# SCH_Rydful-Beacon_2026-01-27.net
KiCad netlist of a schematic drawn in EasyEDA
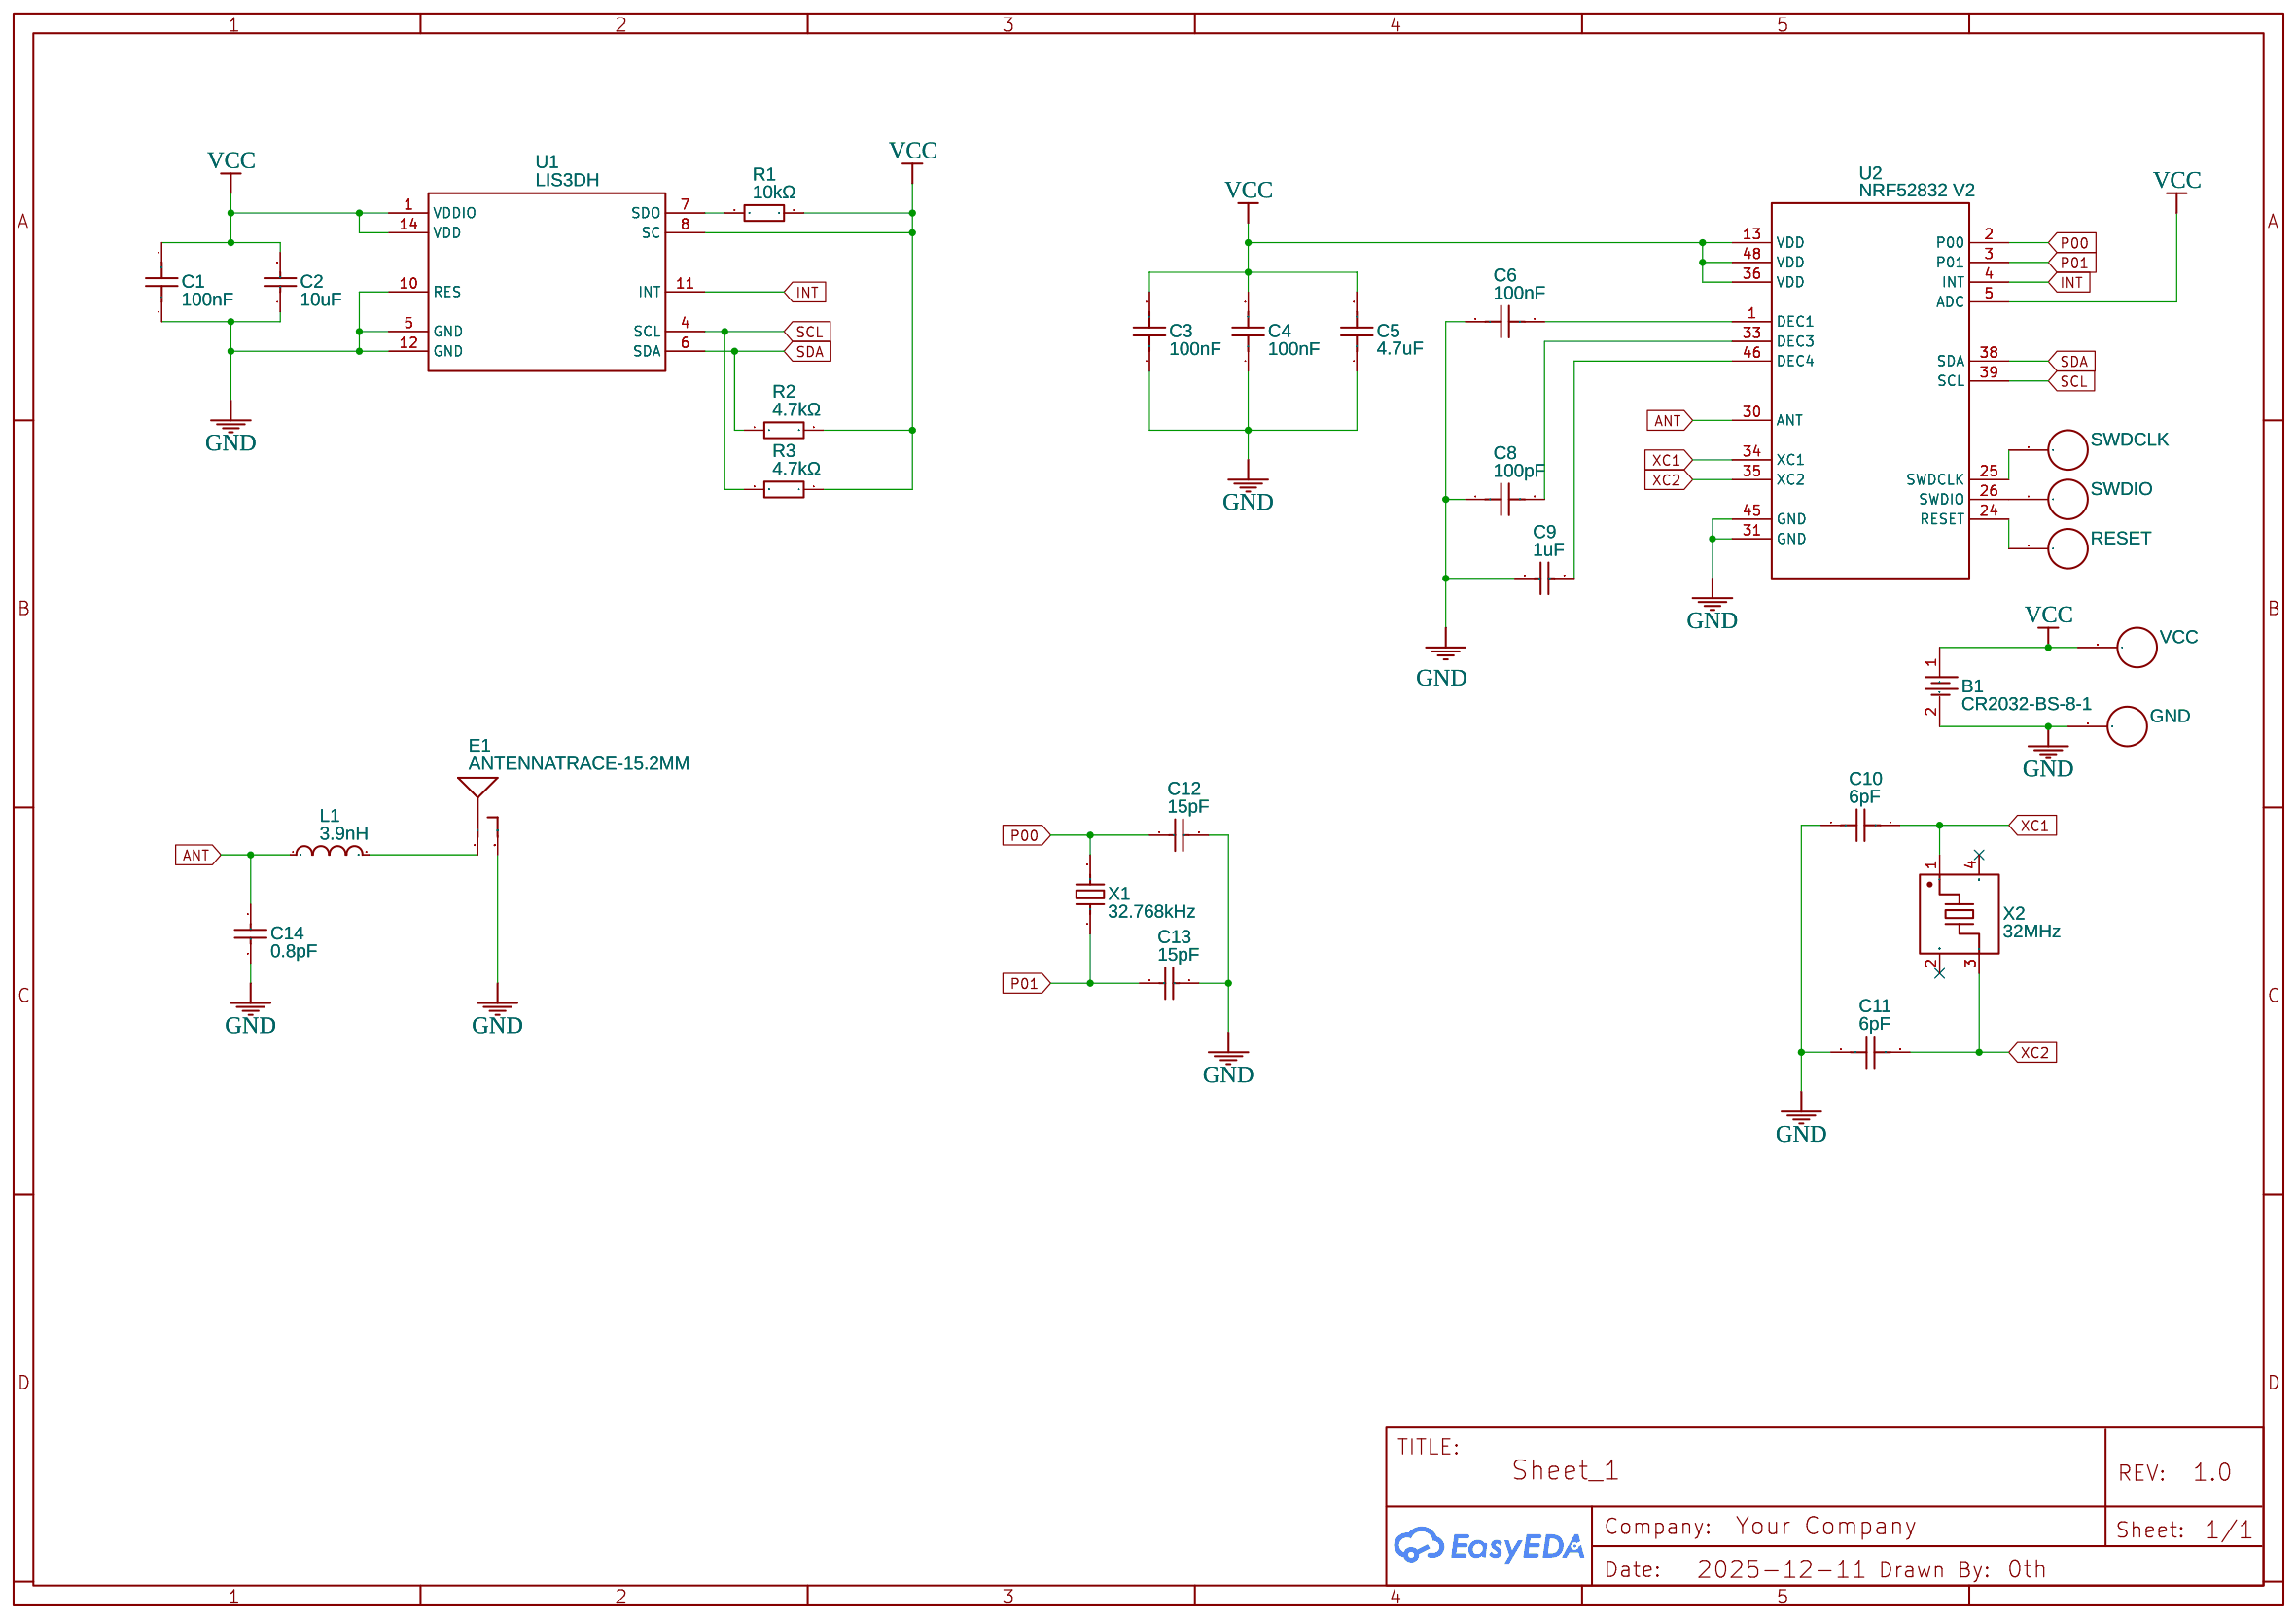
[diagram p0: schematic sheet]

(export (version "E")
  (design (tool "Eeschema 10.0.6"))
  (components
    (comp (ref "B1")
      (value "CR2032-BS-8-1")
      (fields (field (name "Manufacturer Part") "BS-8-1") (field (name "Manufacturer") "QIJEY"))
      (libsource (lib "") (part "CR2032-BS-8-1"))
    )
    (comp (ref "C1") (value "100nF") (libsource (lib "") (part "CC0402KRX7R7BB104")))
    (comp (ref "C2") (value "10uF") (libsource (lib "") (part "0603X106K160NT")))
    (comp (ref "C3") (value "100nF") (libsource (lib "") (part "CC0402KRX7R7BB104")))
    (comp (ref "C4") (value "100nF") (libsource (lib "") (part "CC0402KRX7R7BB104")))
    (comp (ref "C5") (value "4.7uF") (libsource (lib "") (part "CL10A475KO8NNNC")))
    (comp (ref "C6") (value "100nF") (libsource (lib "") (part "CC0402KRX7R7BB104_1")))
    (comp (ref "C8") (value "100pF") (libsource (lib "") (part "CGA0402C0G101J160GT")))
    (comp (ref "C9")
      (value "1uF")
      (fields
        (field (name "Manufacturer Part") "CL05A105KO5NNNC")
        (field (name "Manufacturer") "SAMSUNG(三星)")
      )
      (libsource (lib "") (part "CL05A105KO5NNNC"))
    )
    (comp (ref "C10")
      (value "6pF")
      (fields
        (field (name "Manufacturer Part") "TCC0402COG6R0C500AT")
        (field (name "Manufacturer") "CCTC(三环)")
      )
      (libsource (lib "") (part "TCC0402COG6R0C500AT"))
    )
    (comp (ref "C11")
      (value "6pF")
      (fields
        (field (name "Manufacturer Part") "TCC0402COG6R0C500AT")
        (field (name "Manufacturer") "CCTC(三环)")
      )
      (libsource (lib "") (part "TCC0402COG6R0C500AT"))
    )
    (comp (ref "C12")
      (value "15pF")
      (fields (field (name "Manufacturer Part") "0402CG150J500NT") (field (name "Manufacturer") "FH(风华)"))
      (libsource (lib "") (part "0402CG150J500NT"))
    )
    (comp (ref "C13")
      (value "15pF")
      (fields (field (name "Manufacturer Part") "0402CG150J500NT") (field (name "Manufacturer") "FH(风华)"))
      (libsource (lib "") (part "0402CG150J500NT"))
    )
    (comp (ref "C14")
      (value "0.8pF")
      (fields (field (name "Manufacturer Part") "0402CG0R8C500NT") (field (name "Manufacturer") "FH(风华)"))
      (libsource (lib "") (part "0402CG0R8C500NT"))
    )
    (comp (ref "E1") (value "ANTENNATRACE-15.2MM") (libsource (lib "") (part "ANTENNATRACE-15.2MM")))
    (comp (ref "GND") (value "pad") (libsource (lib "") (part "pad_3")))
    (comp (ref "L1")
      (value "3.9nH")
      (fields (field (name "Manufacturer Part") "LQW15AN3N9B00D") (field (name "Manufacturer") "muRata(村田)"))
      (libsource (lib "") (part "LQW15AN3N9B00D"))
    )
    (comp (ref "R1") (value "10kΩ") (libsource (lib "") (part "0603WAF1002T5E")))
    (comp (ref "R2") (value "4.7kΩ") (libsource (lib "") (part "0603WAF4701T5E")))
    (comp (ref "R3") (value "4.7kΩ") (libsource (lib "") (part "0603WAF4701T5E_1")))
    (comp (ref "RESET") (value "pad") (libsource (lib "") (part "pad_1")))
    (comp (ref "SWDCLK") (value "pad") (libsource (lib "") (part "pad_4")))
    (comp (ref "SWDIO") (value "pad") (libsource (lib "") (part "pad")))
    (comp (ref "U1")
      (value "LIS3DH")
      (fields (field (name "Manufacturer Part") "LIS3DHTR") (field (name "Manufacturer") "ST(意法半导体)"))
      (libsource (lib "") (part "LIS3DH"))
    )
    (comp (ref "U2")
      (value "NRF52832 V2")
      (fields (field (name "Manufacturer Part") "NRF52832-QFAA-R") (field (name "Manufacturer") "NORDIC"))
      (libsource (lib "") (part "NRF52832 V2"))
    )
    (comp (ref "VCC") (value "pad") (libsource (lib "") (part "pad_2")))
    (comp (ref "X1")
      (value "32.768kHz")
      (fields (field (name "Manufacturer Part") "XTF32032768KT00351011") (field (name "Manufacturer") "同晶"))
      (libsource (lib "") (part "XTF32032768KT00351011"))
    )
    (comp (ref "X2")
      (value "32MHz")
      (fields (field (name "Manufacturer Part") "7E32000E09UCG") (field (name "Manufacturer") "SJK(晶科鑫)"))
      (libsource (lib "") (part "7E32000E09UCG"))
    )
  )
  (nets
    (net (code "1") (name "ANT") (class "Default")
      (node (ref "C14") (pin "1") (pinfunction "1_1") (pintype "input"))
      (node (ref "L1") (pin "1") (pinfunction "1_1") (pintype "unspecified"))
      (node (ref "U2") (pin "30") (pinfunction "ANT_30") (pintype "unspecified"))
    )
    (net (code "2") (name "GND") (class "Default")
      (node (ref "B1") (pin "2") (pinfunction "2_2") (pintype "input"))
      (node (ref "C1") (pin "1") (pinfunction "1_1") (pintype "unspecified"))
      (node (ref "C10") (pin "1") (pinfunction "1_1") (pintype "unspecified"))
      (node (ref "C11") (pin "1") (pinfunction "1_1") (pintype "unspecified"))
      (node (ref "C12") (pin "2") (pinfunction "2_2") (pintype "input"))
      (node (ref "C13") (pin "2") (pinfunction "2_2") (pintype "input"))
      (node (ref "C14") (pin "2") (pinfunction "2_2") (pintype "input"))
      (node (ref "C2") (pin "1") (pinfunction "1_1") (pintype "input"))
      (node (ref "C3") (pin "1") (pinfunction "1_1") (pintype "unspecified"))
      (node (ref "C4") (pin "1") (pinfunction "1_1") (pintype "unspecified"))
      (node (ref "C5") (pin "1") (pinfunction "1_1") (pintype "unspecified"))
      (node (ref "C6") (pin "2") (pinfunction "2_2") (pintype "unspecified"))
      (node (ref "C8") (pin "1") (pinfunction "1_1") (pintype "unspecified"))
      (node (ref "C9") (pin "1") (pinfunction "1_1") (pintype "input"))
      (node (ref "E1") (pin "GND") (pinfunction "GND_GND") (pintype "bidirectional"))
      (node (ref "GND") (pin "1") (pinfunction "1_1") (pintype "unspecified"))
      (node (ref "U1") (pin "10") (pinfunction "RES_10") (pintype "unspecified"))
      (node (ref "U1") (pin "12") (pinfunction "GND_12") (pintype "unspecified"))
      (node (ref "U1") (pin "5") (pinfunction "GND_5") (pintype "unspecified"))
      (node (ref "U2") (pin "31") (pinfunction "GND_31") (pintype "unspecified"))
      (node (ref "U2") (pin "45") (pinfunction "GND_45") (pintype "unspecified"))
    )
    (net (code "3") (name "INT") (class "Default")
      (node (ref "U1") (pin "11") (pinfunction "INT_11") (pintype "unspecified"))
      (node (ref "U2") (pin "4") (pinfunction "INT_4") (pintype "unspecified"))
    )
    (net (code "4") (name "Net-(E1-SIGNAL)") (class "Default")
      (node (ref "E1") (pin "ANT") (pinfunction "SIGNAL_ANT") (pintype "bidirectional"))
      (node (ref "L1") (pin "2") (pinfunction "2_2") (pintype "unspecified"))
    )
    (net (code "5") (name "Net-(U1-SDO)") (class "Default")
      (node (ref "R1") (pin "2") (pinfunction "2_2") (pintype "input"))
      (node (ref "U1") (pin "7") (pinfunction "SDO_7") (pintype "unspecified"))
    )
    (net (code "6") (name "Net-(U2-DEC1)") (class "Default")
      (node (ref "C6") (pin "1") (pinfunction "1_1") (pintype "unspecified"))
      (node (ref "U2") (pin "1") (pinfunction "DEC1_1") (pintype "unspecified"))
    )
    (net (code "7") (name "Net-(U2-DEC3)") (class "Default")
      (node (ref "C8") (pin "2") (pinfunction "2_2") (pintype "unspecified"))
      (node (ref "U2") (pin "33") (pinfunction "DEC3_33") (pintype "unspecified"))
    )
    (net (code "8") (name "Net-(U2-DEC4)") (class "Default")
      (node (ref "C9") (pin "2") (pinfunction "2_2") (pintype "input"))
      (node (ref "U2") (pin "46") (pinfunction "DEC4_46") (pintype "unspecified"))
    )
    (net (code "9") (name "Net-(U2-RESET)") (class "Default")
      (node (ref "RESET") (pin "1") (pinfunction "1_1") (pintype "unspecified"))
      (node (ref "U2") (pin "24") (pinfunction "RESET_24") (pintype "unspecified"))
    )
    (net (code "10") (name "Net-(U2-SWDCLK)") (class "Default")
      (node (ref "SWDCLK") (pin "1") (pinfunction "1_1") (pintype "unspecified"))
      (node (ref "U2") (pin "25") (pinfunction "SWDCLK_25") (pintype "unspecified"))
    )
    (net (code "11") (name "Net-(U2-SWDIO)") (class "Default")
      (node (ref "SWDIO") (pin "1") (pinfunction "1_1") (pintype "unspecified"))
      (node (ref "U2") (pin "26") (pinfunction "SWDIO_26") (pintype "unspecified"))
    )
    (net (code "12") (name "P00") (class "Default")
      (node (ref "C12") (pin "1") (pinfunction "1_1") (pintype "input"))
      (node (ref "U2") (pin "2") (pinfunction "P00_2") (pintype "unspecified"))
      (node (ref "X1") (pin "2") (pinfunction "2_2") (pintype "input"))
    )
    (net (code "13") (name "P01") (class "Default")
      (node (ref "C13") (pin "1") (pinfunction "1_1") (pintype "input"))
      (node (ref "U2") (pin "3") (pinfunction "P01_3") (pintype "unspecified"))
      (node (ref "X1") (pin "1") (pinfunction "1_1") (pintype "input"))
    )
    (net (code "14") (name "SCL") (class "Default")
      (node (ref "R3") (pin "2") (pinfunction "2_2") (pintype "input"))
      (node (ref "U1") (pin "4") (pinfunction "SCL_4") (pintype "unspecified"))
      (node (ref "U2") (pin "39") (pinfunction "SCL_39") (pintype "unspecified"))
    )
    (net (code "15") (name "SDA") (class "Default")
      (node (ref "R2") (pin "1") (pinfunction "1_1") (pintype "input"))
      (node (ref "U1") (pin "6") (pinfunction "SDA_6") (pintype "unspecified"))
      (node (ref "U2") (pin "38") (pinfunction "SDA_38") (pintype "unspecified"))
    )
    (net (code "16") (name "VCC") (class "Default")
      (node (ref "B1") (pin "1") (pinfunction "1_1") (pintype "input"))
      (node (ref "C1") (pin "2") (pinfunction "2_2") (pintype "unspecified"))
      (node (ref "C2") (pin "2") (pinfunction "2_2") (pintype "input"))
      (node (ref "C3") (pin "2") (pinfunction "2_2") (pintype "unspecified"))
      (node (ref "C4") (pin "2") (pinfunction "2_2") (pintype "unspecified"))
      (node (ref "C5") (pin "2") (pinfunction "2_2") (pintype "unspecified"))
      (node (ref "R1") (pin "1") (pinfunction "1_1") (pintype "input"))
      (node (ref "R2") (pin "2") (pinfunction "2_2") (pintype "input"))
      (node (ref "R3") (pin "1") (pinfunction "1_1") (pintype "input"))
      (node (ref "U1") (pin "1") (pinfunction "VDDIO_1") (pintype "unspecified"))
      (node (ref "U1") (pin "14") (pinfunction "VDD_14") (pintype "unspecified"))
      (node (ref "U1") (pin "8") (pinfunction "SC_8") (pintype "unspecified"))
      (node (ref "U2") (pin "13") (pinfunction "VDD_13") (pintype "unspecified"))
      (node (ref "U2") (pin "36") (pinfunction "VDD_36") (pintype "unspecified"))
      (node (ref "U2") (pin "48") (pinfunction "VDD_48") (pintype "unspecified"))
      (node (ref "U2") (pin "5") (pinfunction "ADC_5") (pintype "unspecified"))
      (node (ref "VCC") (pin "1") (pinfunction "1_1") (pintype "unspecified"))
    )
    (net (code "17") (name "XC1") (class "Default")
      (node (ref "C10") (pin "2") (pinfunction "2_2") (pintype "unspecified"))
      (node (ref "U2") (pin "34") (pinfunction "XC1_34") (pintype "unspecified"))
      (node (ref "X2") (pin "1") (pinfunction "1_1") (pintype "input"))
    )
    (net (code "18") (name "XC2") (class "Default")
      (node (ref "C11") (pin "2") (pinfunction "2_2") (pintype "unspecified"))
      (node (ref "U2") (pin "35") (pinfunction "XC2_35") (pintype "unspecified"))
      (node (ref "X2") (pin "3") (pinfunction "3_3") (pintype "input"))
    )
    (net (code "19") (name "unconnected-(X2-GND-Pad2)") (class "Default")
      (node (ref "X2") (pin "2") (pinfunction "GND_2") (pintype "input+no_connect"))
    )
    (net (code "20") (name "unconnected-(X2-GND-Pad4)") (class "Default")
      (node (ref "X2") (pin "4") (pinfunction "GND_4") (pintype "input+no_connect"))
    )
  )
)
